# SCH_Tiny_printer_small_2024-09-06.net
KiCad netlist of a schematic drawn in EasyEDA
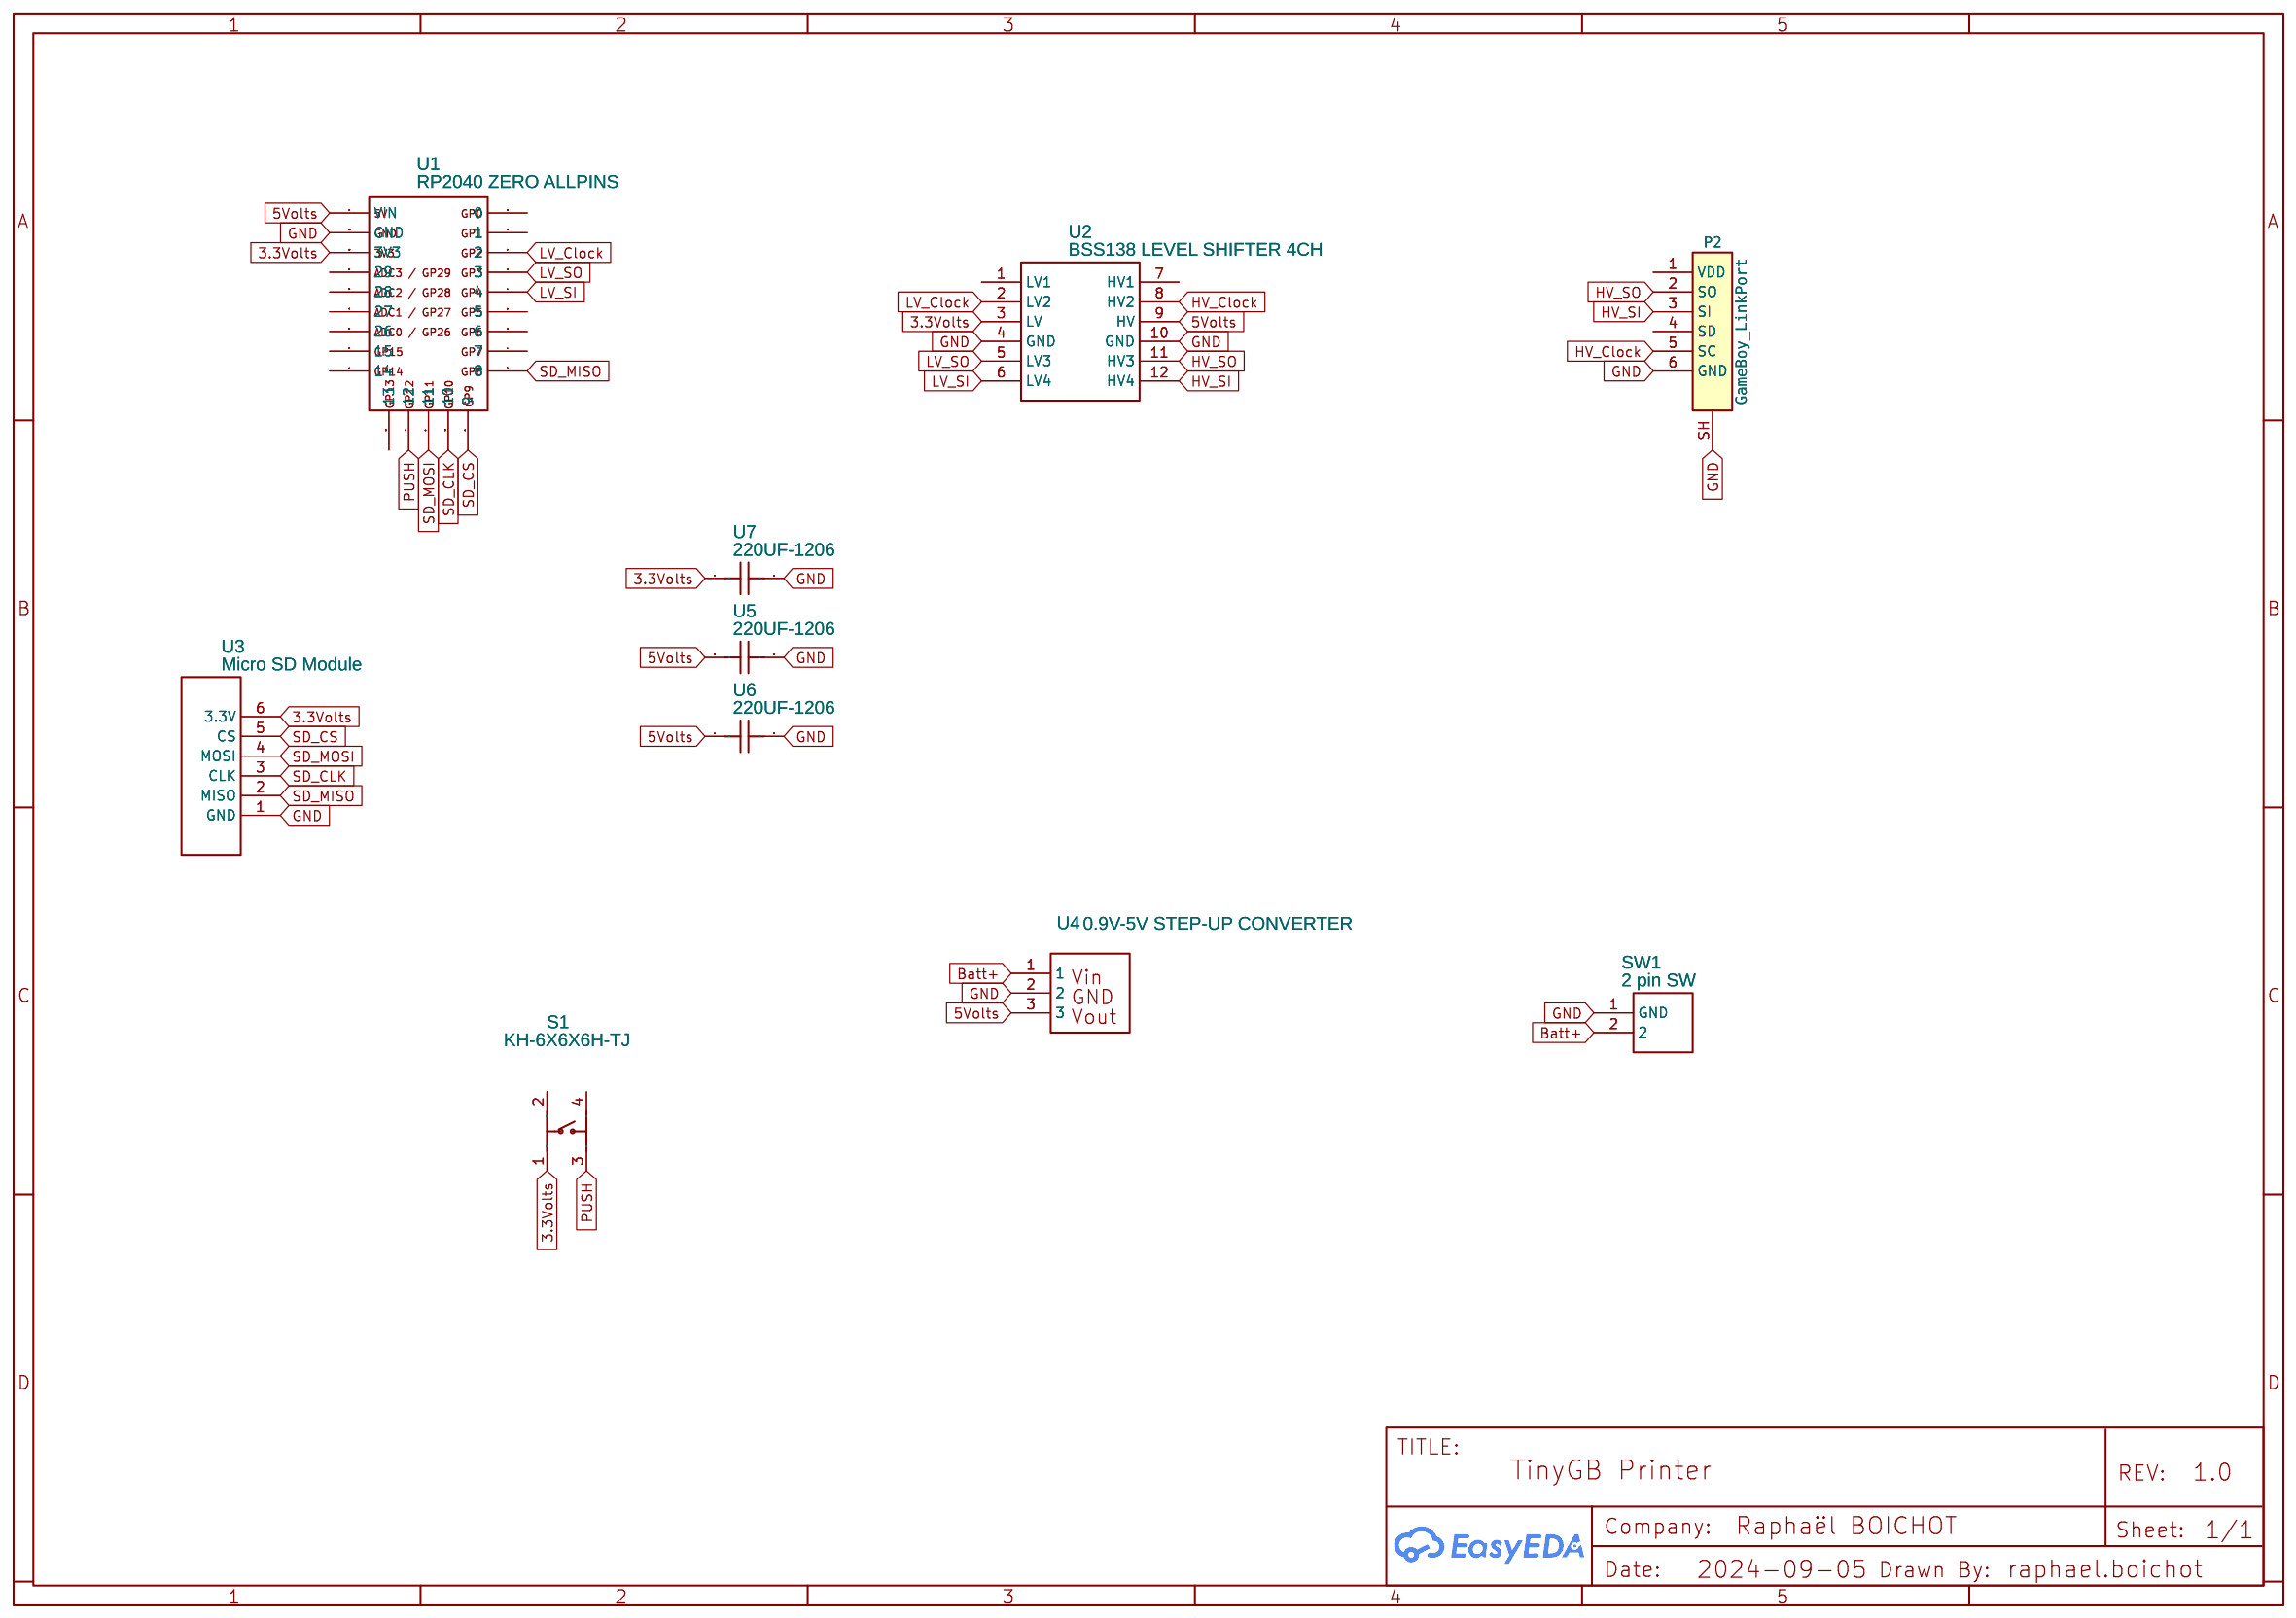
[diagram p0: schematic sheet]

(export (version "E")
  (design (tool "Eeschema 10.0.6"))
  (components
    (comp (ref "P2") (value "GameBoy_LinkPort") (libsource (lib "") (part "Unknown_860_-645")))
    (comp (ref "S1")
      (value "KH-6X6X6H-TJ")
      (fields (field (name "Manufacturer") "kinghelm(金航标)"))
      (libsource (lib "") (part "KH-6X6X6H-TJ"))
    )
    (comp (ref "SW1")
      (value "2 pin SW")
      (fields (field (name "Manufacturer") "NA"))
      (libsource (lib "") (part "2 pin SW"))
    )
    (comp (ref "U1")
      (value "RP2040 ZERO ALLPINS")
      (fields (field (name "Manufacturer Part") "RP2040 Zero") (field (name "Manufacturer") "Waveshare"))
      (libsource (lib "") (part "RP2040 ZERO ALLPINS"))
    )
    (comp (ref "U2")
      (value "BSS138 LEVEL SHIFTER 4CH")
      (fields (field (name "Manufacturer Part") "BSS138") (field (name "Manufacturer") "ON Semiconductor"))
      (libsource (lib "") (part "BSS138 LEVEL SHIFTER 4CH"))
    )
    (comp (ref "U3") (value "Micro SD Module") (libsource (lib "") (part "Micro SD Module")))
    (comp (ref "U4")
      (value "0.9V-5V STEP-UP CONVERTER")
      (fields (field (name "Manufacturer") "Generic"))
      (libsource (lib "") (part "0.9V-5V STEP-UP CONVERTER"))
    )
    (comp (ref "U5") (value "220UF-1206") (libsource (lib "") (part "220UF-1206")))
    (comp (ref "U6") (value "220UF-1206") (libsource (lib "") (part "220UF-1206")))
    (comp (ref "U7") (value "220UF-1206") (libsource (lib "") (part "220UF-1206")))
  )
  (nets
    (net (code "1") (name "3.3Volts") (class "Default")
      (node (ref "S1") (pin "1") (pinfunction "1_1") (pintype "unspecified"))
      (node (ref "U1") (pin "3V3") (pinfunction "3V3_3V3") (pintype "unspecified"))
      (node (ref "U2") (pin "3") (pinfunction "LV_3") (pintype "passive"))
      (node (ref "U3") (pin "6") (pinfunction "3.3V_6") (pintype "unspecified"))
      (node (ref "U7") (pin "1") (pinfunction "1_1") (pintype "unspecified"))
    )
    (net (code "2") (name "5Volts") (class "Default")
      (node (ref "U1") (pin "VIN") (pinfunction "VIN_VIN") (pintype "unspecified"))
      (node (ref "U2") (pin "9") (pinfunction "HV_9") (pintype "passive"))
      (node (ref "U4") (pin "3") (pinfunction "3_3") (pintype "unspecified"))
      (node (ref "U5") (pin "1") (pinfunction "1_1") (pintype "unspecified"))
      (node (ref "U6") (pin "1") (pinfunction "1_1") (pintype "unspecified"))
    )
    (net (code "3") (name "Batt+") (class "Default")
      (node (ref "SW1") (pin "2") (pinfunction "2_2") (pintype "unspecified"))
      (node (ref "U4") (pin "1") (pinfunction "1_1") (pintype "unspecified"))
    )
    (net (code "4") (name "GND") (class "Default")
      (node (ref "P2") (pin "6") (pinfunction "GND_6") (pintype "unspecified"))
      (node (ref "P2") (pin "SH") (pintype "unspecified"))
      (node (ref "SW1") (pin "1") (pinfunction "GND_1") (pintype "unspecified"))
      (node (ref "U1") (pin "GND") (pinfunction "GND_GND") (pintype "unspecified"))
      (node (ref "U2") (pin "10") (pinfunction "GND_10") (pintype "passive"))
      (node (ref "U2") (pin "4") (pinfunction "GND_4") (pintype "passive"))
      (node (ref "U3") (pin "1") (pinfunction "GND_1") (pintype "unspecified"))
      (node (ref "U4") (pin "2") (pinfunction "2_2") (pintype "unspecified"))
      (node (ref "U5") (pin "2") (pinfunction "2_2") (pintype "unspecified"))
      (node (ref "U6") (pin "2") (pinfunction "2_2") (pintype "unspecified"))
      (node (ref "U7") (pin "2") (pinfunction "2_2") (pintype "unspecified"))
    )
    (net (code "5") (name "HV_Clock") (class "Default")
      (node (ref "P2") (pin "5") (pinfunction "SC_5") (pintype "unspecified"))
      (node (ref "U2") (pin "8") (pinfunction "HV2_8") (pintype "output"))
    )
    (net (code "6") (name "HV_SI") (class "Default")
      (node (ref "P2") (pin "3") (pinfunction "SI_3") (pintype "unspecified"))
      (node (ref "U2") (pin "12") (pinfunction "HV4_12") (pintype "output"))
    )
    (net (code "7") (name "HV_SO") (class "Default")
      (node (ref "P2") (pin "2") (pinfunction "SO_2") (pintype "unspecified"))
      (node (ref "U2") (pin "11") (pinfunction "HV3_11") (pintype "output"))
    )
    (net (code "8") (name "LV_Clock") (class "Default")
      (node (ref "U1") (pin "2") (pinfunction "2_2") (pintype "unspecified"))
      (node (ref "U2") (pin "2") (pinfunction "LV2_2") (pintype "input"))
    )
    (net (code "9") (name "LV_SI") (class "Default")
      (node (ref "U1") (pin "4") (pinfunction "4_4") (pintype "unspecified"))
      (node (ref "U2") (pin "6") (pinfunction "LV4_6") (pintype "input"))
    )
    (net (code "10") (name "LV_SO") (class "Default")
      (node (ref "U1") (pin "3") (pinfunction "3_3") (pintype "unspecified"))
      (node (ref "U2") (pin "5") (pinfunction "LV3_5") (pintype "input"))
    )
    (net (code "11") (name "PUSH") (class "Default")
      (node (ref "S1") (pin "3") (pinfunction "3_3") (pintype "unspecified"))
      (node (ref "U1") (pin "12") (pinfunction "12_12") (pintype "unspecified"))
    )
    (net (code "12") (name "SD_CLK") (class "Default")
      (node (ref "U1") (pin "10") (pinfunction "10_10") (pintype "unspecified"))
      (node (ref "U3") (pin "3") (pinfunction "CLK_3") (pintype "unspecified"))
    )
    (net (code "13") (name "SD_CS") (class "Default")
      (node (ref "U1") (pin "9") (pinfunction "9_9") (pintype "unspecified"))
      (node (ref "U3") (pin "5") (pinfunction "CS_5") (pintype "unspecified"))
    )
    (net (code "14") (name "SD_MISO") (class "Default")
      (node (ref "U1") (pin "8") (pinfunction "8_8") (pintype "unspecified"))
      (node (ref "U3") (pin "2") (pinfunction "MISO_2") (pintype "unspecified"))
    )
    (net (code "15") (name "SD_MOSI") (class "Default")
      (node (ref "U1") (pin "11") (pinfunction "11_11") (pintype "unspecified"))
      (node (ref "U3") (pin "4") (pinfunction "MOSI_4") (pintype "unspecified"))
    )
    (net (code "16") (name "unconnected-(P2-SD-Pad4)") (class "Default")
      (node (ref "P2") (pin "4") (pinfunction "SD_4") (pintype "unspecified"))
    )
    (net (code "17") (name "unconnected-(P2-VDD-Pad1)") (class "Default")
      (node (ref "P2") (pin "1") (pinfunction "VDD_1") (pintype "unspecified"))
    )
    (net (code "18") (name "unconnected-(S1-Pad2)") (class "Default")
      (node (ref "S1") (pin "2") (pinfunction "2_2") (pintype "unspecified"))
    )
    (net (code "19") (name "unconnected-(S1-Pad4)") (class "Default")
      (node (ref "S1") (pin "4") (pinfunction "4_4") (pintype "unspecified"))
    )
    (net (code "20") (name "unconnected-(U1-Pad0)") (class "Default")
      (node (ref "U1") (pin "0") (pinfunction "0_0") (pintype "unspecified"))
    )
    (net (code "21") (name "unconnected-(U1-Pad1)") (class "Default")
      (node (ref "U1") (pin "1") (pinfunction "1_1") (pintype "unspecified"))
    )
    (net (code "22") (name "unconnected-(U1-Pad5)") (class "Default")
      (node (ref "U1") (pin "5") (pinfunction "5_5") (pintype "unspecified"))
    )
    (net (code "23") (name "unconnected-(U1-Pad6)") (class "Default")
      (node (ref "U1") (pin "6") (pinfunction "6_6") (pintype "unspecified"))
    )
    (net (code "24") (name "unconnected-(U1-Pad7)") (class "Default")
      (node (ref "U1") (pin "7") (pinfunction "7_7") (pintype "unspecified"))
    )
    (net (code "25") (name "unconnected-(U1-Pad13)") (class "Default")
      (node (ref "U1") (pin "13") (pinfunction "13_13") (pintype "unspecified"))
    )
    (net (code "26") (name "unconnected-(U1-Pad14)") (class "Default")
      (node (ref "U1") (pin "14") (pinfunction "14_14") (pintype "unspecified"))
    )
    (net (code "27") (name "unconnected-(U1-Pad15)") (class "Default")
      (node (ref "U1") (pin "15") (pinfunction "15_15") (pintype "unspecified"))
    )
    (net (code "28") (name "unconnected-(U1-Pad26)") (class "Default")
      (node (ref "U1") (pin "26") (pinfunction "26_26") (pintype "unspecified"))
    )
    (net (code "29") (name "unconnected-(U1-Pad27)") (class "Default")
      (node (ref "U1") (pin "27") (pinfunction "27_27") (pintype "unspecified"))
    )
    (net (code "30") (name "unconnected-(U1-Pad28)") (class "Default")
      (node (ref "U1") (pin "28") (pinfunction "28_28") (pintype "unspecified"))
    )
    (net (code "31") (name "unconnected-(U1-Pad29)") (class "Default")
      (node (ref "U1") (pin "29") (pinfunction "29_29") (pintype "unspecified"))
    )
    (net (code "32") (name "unconnected-(U2-HV1-Pad7)") (class "Default")
      (node (ref "U2") (pin "7") (pinfunction "HV1_7") (pintype "output"))
    )
    (net (code "33") (name "unconnected-(U2-LV1-Pad1)") (class "Default")
      (node (ref "U2") (pin "1") (pinfunction "LV1_1") (pintype "input"))
    )
  )
)
